# sense_pcb_d.net
KiCad netlist of a schematic drawn in EAGLE
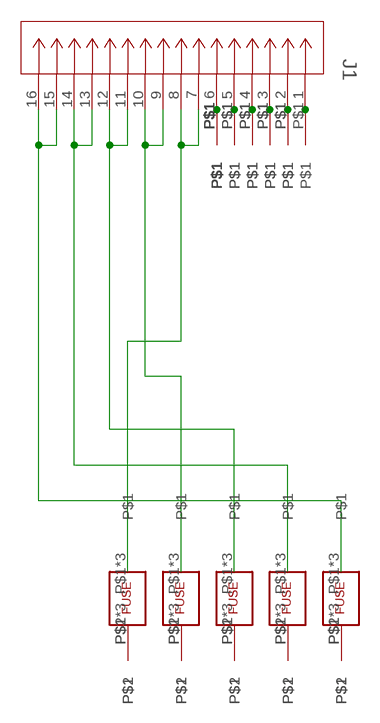
[diagram p0: schematic, sheet 1]

(export (version "E")
  (design (tool "Eeschema 10.0.6"))
  (components
    (comp (ref "J1")
      (value "DF11-16DP-2DSA(01)")
      (footprint "eagle-import:CONN_DF11-16DP-2DSA(01)_HIR")
      (fields (field (name "COPYRIGHT") "Copyright (C) 2023 Ultra Librarian. All rights reserved."))
      (libsource (lib "eagle-import") (part "DF11-16DP-2DSA(01)"))
    )
    (comp (ref "U$1")
      (value "FUSE")
      (footprint "eagle-import:FUSE_PADS")
      (libsource (lib "eagle-import") (part "FUSE"))
    )
    (comp (ref "U$2")
      (value "FUSE")
      (footprint "eagle-import:FUSE_PADS")
      (libsource (lib "eagle-import") (part "FUSE"))
    )
    (comp (ref "U$3")
      (value "FUSE")
      (footprint "eagle-import:FUSE_PADS")
      (libsource (lib "eagle-import") (part "FUSE"))
    )
    (comp (ref "U$4")
      (value "FUSE")
      (footprint "eagle-import:FUSE_PADS")
      (libsource (lib "eagle-import") (part "FUSE"))
    )
    (comp (ref "U$5")
      (value "FUSE")
      (footprint "eagle-import:FUSE_PADS")
      (libsource (lib "eagle-import") (part "FUSE"))
    )
    (comp (ref "U$6")
      (value "BB_CONTACT")
      (footprint "eagle-import:BB_CONTACT")
      (libsource (lib "eagle-import") (part "BB_CONTACT"))
    )
    (comp (ref "U$7")
      (value "BB_CONTACT")
      (footprint "eagle-import:BB_CONTACT")
      (libsource (lib "eagle-import") (part "BB_CONTACT"))
    )
    (comp (ref "U$8")
      (value "BB_CONTACT")
      (footprint "eagle-import:BB_CONTACT")
      (libsource (lib "eagle-import") (part "BB_CONTACT"))
    )
    (comp (ref "U$9")
      (value "BB_CONTACT")
      (footprint "eagle-import:BB_CONTACT")
      (libsource (lib "eagle-import") (part "BB_CONTACT"))
    )
    (comp (ref "U$10")
      (value "BB_CONTACT")
      (footprint "eagle-import:BB_CONTACT")
      (libsource (lib "eagle-import") (part "BB_CONTACT"))
    )
    (comp (ref "U$12")
      (value "THERM_PIN")
      (footprint "eagle-import:THERM_PIN")
      (libsource (lib "eagle-import") (part "THERM_PIN"))
    )
    (comp (ref "U$13")
      (value "THERM_PIN")
      (footprint "eagle-import:THERM_PIN")
      (libsource (lib "eagle-import") (part "THERM_PIN"))
    )
    (comp (ref "U$14")
      (value "THERM_PIN")
      (footprint "eagle-import:THERM_PIN")
      (libsource (lib "eagle-import") (part "THERM_PIN"))
    )
    (comp (ref "U$15")
      (value "THERM_PIN")
      (footprint "eagle-import:THERM_PIN")
      (libsource (lib "eagle-import") (part "THERM_PIN"))
    )
    (comp (ref "U$16")
      (value "THERM_PIN")
      (footprint "eagle-import:THERM_PIN")
      (libsource (lib "eagle-import") (part "THERM_PIN"))
    )
    (comp (ref "U$17")
      (value "THERM_PIN")
      (footprint "eagle-import:THERM_PIN")
      (libsource (lib "eagle-import") (part "THERM_PIN"))
    )
    (comp (ref "U$18")
      (value "THERM_PIN")
      (footprint "eagle-import:THERM_PIN")
      (libsource (lib "eagle-import") (part "THERM_PIN"))
    )
    (comp (ref "U$19")
      (value "THERM_PIN")
      (footprint "eagle-import:THERM_PIN")
      (libsource (lib "eagle-import") (part "THERM_PIN"))
    )
    (comp (ref "U$20")
      (value "THERM_PIN")
      (footprint "eagle-import:THERM_PIN")
      (libsource (lib "eagle-import") (part "THERM_PIN"))
    )
    (comp (ref "U$22")
      (value "THERM_PIN")
      (footprint "eagle-import:THERM_PIN")
      (libsource (lib "eagle-import") (part "THERM_PIN"))
    )
    (comp (ref "U$23")
      (value "THERM_PIN")
      (footprint "eagle-import:THERM_PIN")
      (libsource (lib "eagle-import") (part "THERM_PIN"))
    )
    (comp (ref "U$24")
      (value "THERM_PIN")
      (footprint "eagle-import:THERM_PIN")
      (libsource (lib "eagle-import") (part "THERM_PIN"))
    )
    (comp (ref "U$25")
      (value "THERM_PIN")
      (footprint "eagle-import:THERM_PIN")
      (libsource (lib "eagle-import") (part "THERM_PIN"))
    )
    (comp (ref "U$26")
      (value "THERM_PIN")
      (footprint "eagle-import:THERM_PIN")
      (libsource (lib "eagle-import") (part "THERM_PIN"))
    )
    (comp (ref "U$27")
      (value "THERM_PIN")
      (footprint "eagle-import:THERM_PIN")
      (libsource (lib "eagle-import") (part "THERM_PIN"))
    )
    (comp (ref "U$28")
      (value "THERM_PIN")
      (footprint "eagle-import:THERM_PIN")
      (libsource (lib "eagle-import") (part "THERM_PIN"))
    )
    (comp (ref "U$29")
      (value "THERM_PIN")
      (footprint "eagle-import:THERM_PIN")
      (libsource (lib "eagle-import") (part "THERM_PIN"))
    )
    (comp (ref "U$30")
      (value "THERM_PIN")
      (footprint "eagle-import:THERM_PIN")
      (libsource (lib "eagle-import") (part "THERM_PIN"))
    )
  )
  (nets
    (net (code "1") (name "Net-(J1-Pad1)") (class "Default")
      (node (ref "J1") (pin "1") (pinfunction "1_1") (pintype "passive"))
      (node (ref "U$30") (pin "P$1") (pinfunction "P$1_P$1") (pintype "bidirectional"))
    )
    (net (code "2") (name "Net-(J1-Pad2)") (class "Default")
      (node (ref "J1") (pin "2") (pinfunction "2_2") (pintype "passive"))
      (node (ref "U$28") (pin "P$1") (pinfunction "P$1_P$1") (pintype "bidirectional"))
      (node (ref "U$29") (pin "P$1") (pinfunction "P$1_P$1") (pintype "bidirectional"))
    )
    (net (code "3") (name "Net-(J1-Pad3)") (class "Default")
      (node (ref "J1") (pin "3") (pinfunction "3_3") (pintype "passive"))
      (node (ref "U$26") (pin "P$1") (pinfunction "P$1_P$1") (pintype "bidirectional"))
      (node (ref "U$27") (pin "P$1") (pinfunction "P$1_P$1") (pintype "bidirectional"))
    )
    (net (code "4") (name "Net-(J1-Pad4)") (class "Default")
      (node (ref "J1") (pin "4") (pinfunction "4_4") (pintype "passive"))
      (node (ref "U$24") (pin "P$1") (pinfunction "P$1_P$1") (pintype "bidirectional"))
      (node (ref "U$25") (pin "P$1") (pinfunction "P$1_P$1") (pintype "bidirectional"))
    )
    (net (code "5") (name "Net-(J1-Pad5)") (class "Default")
      (node (ref "J1") (pin "5") (pinfunction "5_5") (pintype "passive"))
      (node (ref "U$22") (pin "P$1") (pinfunction "P$1_P$1") (pintype "bidirectional"))
      (node (ref "U$23") (pin "P$1") (pinfunction "P$1_P$1") (pintype "bidirectional"))
    )
    (net (code "6") (name "Net-(J1-Pad6)") (class "Default")
      (node (ref "J1") (pin "6") (pinfunction "6_6") (pintype "passive"))
      (node (ref "U$12") (pin "P$1") (pinfunction "P$1_P$1") (pintype "bidirectional"))
      (node (ref "U$13") (pin "P$1") (pinfunction "P$1_P$1") (pintype "bidirectional"))
      (node (ref "U$14") (pin "P$1") (pinfunction "P$1_P$1") (pintype "bidirectional"))
      (node (ref "U$15") (pin "P$1") (pinfunction "P$1_P$1") (pintype "bidirectional"))
      (node (ref "U$16") (pin "P$1") (pinfunction "P$1_P$1") (pintype "bidirectional"))
      (node (ref "U$17") (pin "P$1") (pinfunction "P$1_P$1") (pintype "bidirectional"))
      (node (ref "U$18") (pin "P$1") (pinfunction "P$1_P$1") (pintype "bidirectional"))
      (node (ref "U$19") (pin "P$1") (pinfunction "P$1_P$1") (pintype "bidirectional"))
      (node (ref "U$20") (pin "P$1") (pinfunction "P$1_P$1") (pintype "bidirectional"))
    )
    (net (code "7") (name "Net-(J1-Pad7)") (class "Default")
      (node (ref "J1") (pin "7") (pinfunction "7_7") (pintype "passive"))
      (node (ref "J1") (pin "8") (pinfunction "8_8") (pintype "passive"))
      (node (ref "U$1") (pin "P$1") (pinfunction "P$1_P$1") (pintype "bidirectional"))
      (node (ref "U$1") (pin "P$3") (pinfunction "P$1_P$3") (pintype "bidirectional"))
      (node (ref "U$1") (pin "P$5") (pinfunction "P$1_P$5") (pintype "bidirectional"))
    )
    (net (code "8") (name "Net-(J1-Pad10)") (class "Default")
      (node (ref "J1") (pin "10") (pinfunction "10_10") (pintype "passive"))
      (node (ref "J1") (pin "9") (pinfunction "9_9") (pintype "passive"))
      (node (ref "U$2") (pin "P$1") (pinfunction "P$1_P$1") (pintype "bidirectional"))
      (node (ref "U$2") (pin "P$3") (pinfunction "P$1_P$3") (pintype "bidirectional"))
      (node (ref "U$2") (pin "P$5") (pinfunction "P$1_P$5") (pintype "bidirectional"))
    )
    (net (code "9") (name "Net-(J1-Pad11)") (class "Default")
      (node (ref "J1") (pin "11") (pinfunction "11_11") (pintype "passive"))
      (node (ref "J1") (pin "12") (pinfunction "12_12") (pintype "passive"))
      (node (ref "U$3") (pin "P$1") (pinfunction "P$1_P$1") (pintype "bidirectional"))
      (node (ref "U$3") (pin "P$3") (pinfunction "P$1_P$3") (pintype "bidirectional"))
      (node (ref "U$3") (pin "P$5") (pinfunction "P$1_P$5") (pintype "bidirectional"))
    )
    (net (code "10") (name "Net-(J1-Pad13)") (class "Default")
      (node (ref "J1") (pin "13") (pinfunction "13_13") (pintype "passive"))
      (node (ref "J1") (pin "14") (pinfunction "14_14") (pintype "passive"))
      (node (ref "U$4") (pin "P$1") (pinfunction "P$1_P$1") (pintype "bidirectional"))
      (node (ref "U$4") (pin "P$3") (pinfunction "P$1_P$3") (pintype "bidirectional"))
      (node (ref "U$4") (pin "P$5") (pinfunction "P$1_P$5") (pintype "bidirectional"))
    )
    (net (code "11") (name "Net-(J1-Pad15)") (class "Default")
      (node (ref "J1") (pin "15") (pinfunction "15_15") (pintype "passive"))
      (node (ref "J1") (pin "16") (pinfunction "16_16") (pintype "passive"))
      (node (ref "U$5") (pin "P$1") (pinfunction "P$1_P$1") (pintype "bidirectional"))
      (node (ref "U$5") (pin "P$3") (pinfunction "P$1_P$3") (pintype "bidirectional"))
      (node (ref "U$5") (pin "P$5") (pinfunction "P$1_P$5") (pintype "bidirectional"))
    )
    (net (code "12") (name "Net-(U$1-P$2-PadP$4)") (class "Default")
      (node (ref "U$1") (pin "P$2") (pinfunction "P$2_P$2") (pintype "bidirectional"))
      (node (ref "U$1") (pin "P$4") (pinfunction "P$2_P$4") (pintype "bidirectional"))
      (node (ref "U$1") (pin "P$6") (pinfunction "P$2_P$6") (pintype "bidirectional"))
      (node (ref "U$6") (pin "P$1") (pinfunction "P$1_P$1") (pintype "bidirectional"))
    )
    (net (code "13") (name "Net-(U$2-P$2-PadP$4)") (class "Default")
      (node (ref "U$2") (pin "P$2") (pinfunction "P$2_P$2") (pintype "bidirectional"))
      (node (ref "U$2") (pin "P$4") (pinfunction "P$2_P$4") (pintype "bidirectional"))
      (node (ref "U$2") (pin "P$6") (pinfunction "P$2_P$6") (pintype "bidirectional"))
      (node (ref "U$7") (pin "P$1") (pinfunction "P$1_P$1") (pintype "bidirectional"))
    )
    (net (code "14") (name "Net-(U$3-P$2-PadP$4)") (class "Default")
      (node (ref "U$3") (pin "P$2") (pinfunction "P$2_P$2") (pintype "bidirectional"))
      (node (ref "U$3") (pin "P$4") (pinfunction "P$2_P$4") (pintype "bidirectional"))
      (node (ref "U$3") (pin "P$6") (pinfunction "P$2_P$6") (pintype "bidirectional"))
      (node (ref "U$8") (pin "P$1") (pinfunction "P$1_P$1") (pintype "bidirectional"))
    )
    (net (code "15") (name "Net-(U$4-P$2-PadP$4)") (class "Default")
      (node (ref "U$4") (pin "P$2") (pinfunction "P$2_P$2") (pintype "bidirectional"))
      (node (ref "U$4") (pin "P$4") (pinfunction "P$2_P$4") (pintype "bidirectional"))
      (node (ref "U$4") (pin "P$6") (pinfunction "P$2_P$6") (pintype "bidirectional"))
      (node (ref "U$9") (pin "P$1") (pinfunction "P$1_P$1") (pintype "bidirectional"))
    )
    (net (code "16") (name "Net-(U$10-PadP$1)") (class "Default")
      (node (ref "U$10") (pin "P$1") (pinfunction "P$1_P$1") (pintype "bidirectional"))
      (node (ref "U$5") (pin "P$2") (pinfunction "P$2_P$2") (pintype "bidirectional"))
      (node (ref "U$5") (pin "P$4") (pinfunction "P$2_P$4") (pintype "bidirectional"))
      (node (ref "U$5") (pin "P$6") (pinfunction "P$2_P$6") (pintype "bidirectional"))
    )
  )
)
